# opt_isp6_prg_header.net
KiCad netlist of a schematic drawn in EAGLE
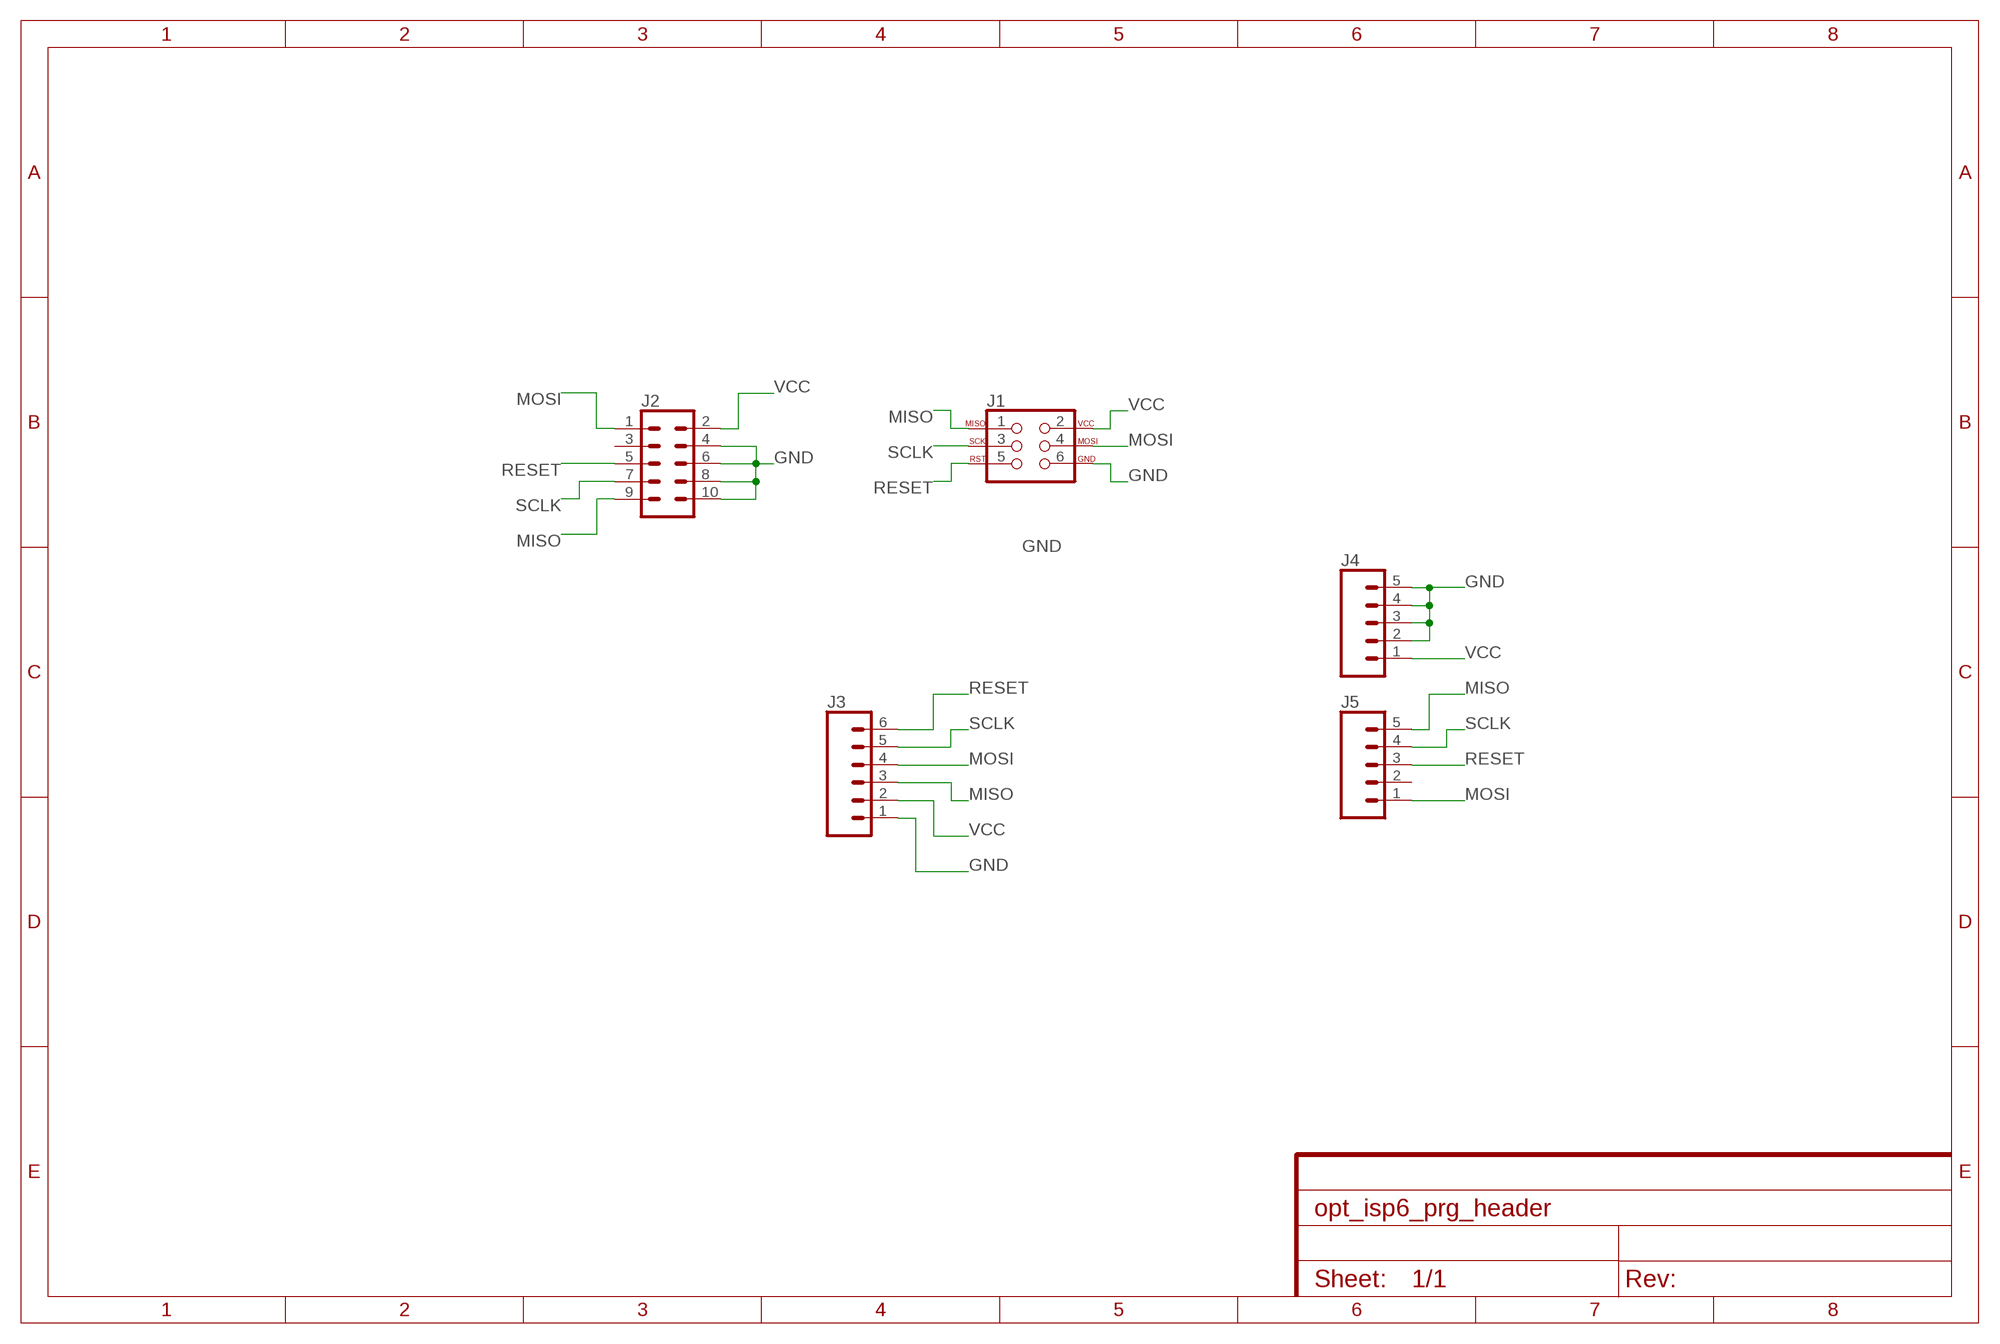
[diagram p0: schematic, sheet 1]

(export (version "E")
  (design (tool "Eeschema 10.0.6"))
  (components
    (comp (ref "J1")
      (value "AVR_SPI_PROG_3X2NS")
      (footprint "eagle-import:2X3-NS")
      (libsource (lib "eagle-import") (part "AVR_SPI_PROG_3X2NS"))
    )
    (comp (ref "J2")
      (value "CONN_05X2SHD")
      (footprint "eagle-import:2X5-SHROUDED")
      (libsource (lib "eagle-import") (part "CONN_05X2SHD"))
    )
    (comp (ref "J3")
      (value "CONN_06NO_SILK_NO_POP")
      (footprint "eagle-import:1X06_NO_SILK")
      (libsource (lib "eagle-import") (part "CONN_06NO_SILK_NO_POP"))
    )
    (comp (ref "J4")
      (value "CONN_05VERT_FEMALE_HEADER")
      (footprint "eagle-import:1X05_SMD_VERTICAL_COMBO")
      (libsource (lib "eagle-import") (part "CONN_05VERT_FEMALE_HEADER"))
    )
    (comp (ref "J5")
      (value "CONN_05VERT_FEMALE_HEADER")
      (footprint "eagle-import:1X05_SMD_VERTICAL_COMBO")
      (libsource (lib "eagle-import") (part "CONN_05VERT_FEMALE_HEADER"))
    )
  )
  (nets
    (net (code "1") (name "/GND") (class "Default")
      (node (ref "J1") (pin "6") (pinfunction "6_6") (pintype "passive"))
      (node (ref "J2") (pin "10") (pinfunction "10_10") (pintype "passive"))
      (node (ref "J2") (pin "4") (pinfunction "4_4") (pintype "passive"))
      (node (ref "J2") (pin "6") (pinfunction "6_6") (pintype "passive"))
      (node (ref "J2") (pin "8") (pinfunction "8_8") (pintype "passive"))
      (node (ref "J3") (pin "1") (pinfunction "1_1") (pintype "passive"))
      (node (ref "J4") (pin "2") (pinfunction "2_2") (pintype "passive"))
      (node (ref "J4") (pin "3") (pinfunction "3_3") (pintype "passive"))
      (node (ref "J4") (pin "4") (pinfunction "4_4") (pintype "passive"))
      (node (ref "J4") (pin "5") (pinfunction "5_5") (pintype "passive"))
    )
    (net (code "2") (name "/MISO") (class "Default")
      (node (ref "J1") (pin "1") (pinfunction "1_1") (pintype "passive"))
      (node (ref "J2") (pin "9") (pinfunction "9_9") (pintype "passive"))
      (node (ref "J3") (pin "3") (pinfunction "3_3") (pintype "passive"))
      (node (ref "J5") (pin "5") (pinfunction "5_5") (pintype "passive"))
    )
    (net (code "3") (name "/MOSI") (class "Default")
      (node (ref "J1") (pin "4") (pinfunction "4_4") (pintype "passive"))
      (node (ref "J2") (pin "1") (pinfunction "1_1") (pintype "passive"))
      (node (ref "J3") (pin "4") (pinfunction "4_4") (pintype "passive"))
      (node (ref "J5") (pin "1") (pinfunction "1_1") (pintype "passive"))
    )
    (net (code "4") (name "/RESET") (class "Default")
      (node (ref "J1") (pin "5") (pinfunction "5_5") (pintype "passive"))
      (node (ref "J2") (pin "5") (pinfunction "5_5") (pintype "passive"))
      (node (ref "J3") (pin "6") (pinfunction "6_6") (pintype "passive"))
      (node (ref "J5") (pin "3") (pinfunction "3_3") (pintype "passive"))
    )
    (net (code "5") (name "/SCLK") (class "Default")
      (node (ref "J1") (pin "3") (pinfunction "3_3") (pintype "passive"))
      (node (ref "J2") (pin "7") (pinfunction "7_7") (pintype "passive"))
      (node (ref "J3") (pin "5") (pinfunction "5_5") (pintype "passive"))
      (node (ref "J5") (pin "4") (pinfunction "4_4") (pintype "passive"))
    )
    (net (code "6") (name "/VCC") (class "Default")
      (node (ref "J1") (pin "2") (pinfunction "2_2") (pintype "passive"))
      (node (ref "J2") (pin "2") (pinfunction "2_2") (pintype "passive"))
      (node (ref "J3") (pin "2") (pinfunction "2_2") (pintype "passive"))
      (node (ref "J4") (pin "1") (pinfunction "1_1") (pintype "passive"))
    )
    (net (code "7") (name "unconnected-(J2-Pad3)") (class "Default")
      (node (ref "J2") (pin "3") (pinfunction "3_3") (pintype "passive"))
    )
    (net (code "8") (name "unconnected-(J5-Pad2)") (class "Default")
      (node (ref "J5") (pin "2") (pinfunction "2_2") (pintype "passive"))
    )
  )
)
